# 36mm____V1_3.net
KiCad netlist of a schematic drawn in EasyEDA Pro
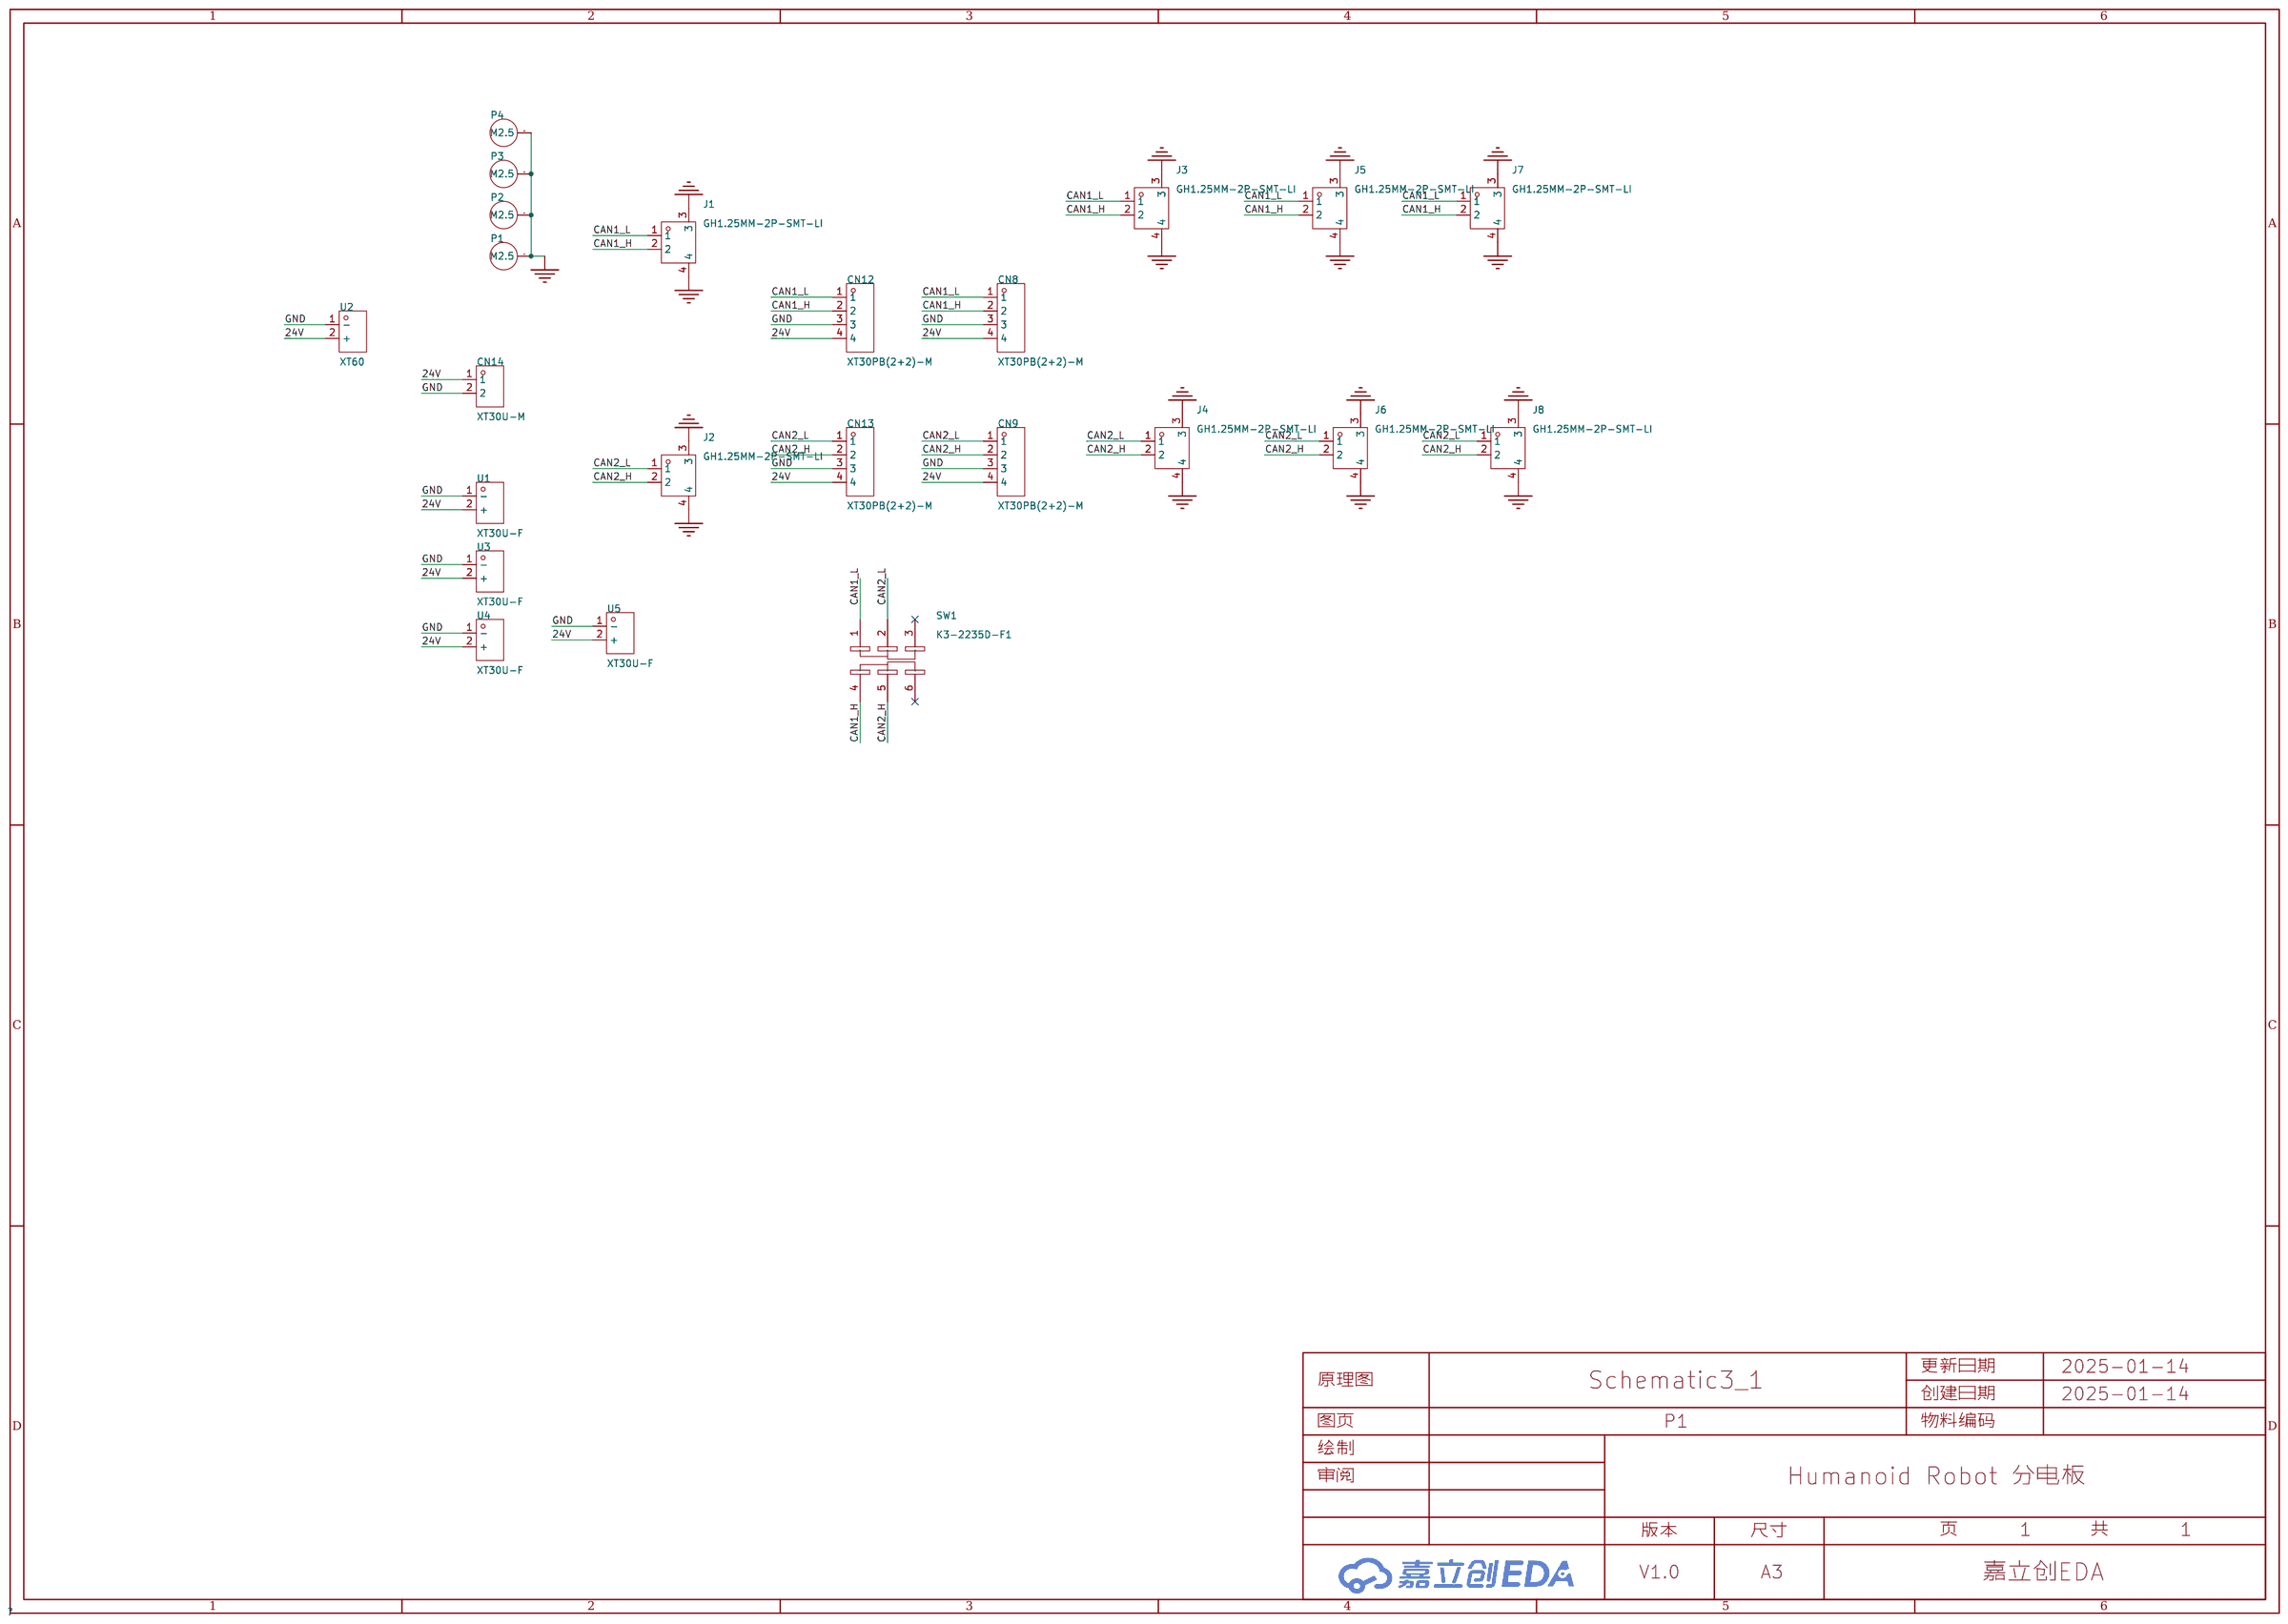
[diagram p0: schematic sheet]

(export (version "E")
  (design (tool "Eeschema 10.0.6"))
  (components
    (comp (ref "CN8")
      (value "XT30PB(2+2)-M")
      (footprint "easyedapro:CONN-TH_XT30PB-M")
      (fields (field (name "Manufacturer") "AMASS(艾迈斯)"))
      (libsource (lib "easyedapro") (part "XT30PB(2+2)-M"))
    )
    (comp (ref "CN9")
      (value "XT30PB(2+2)-M")
      (footprint "easyedapro:CONN-TH_XT30PB-M")
      (fields (field (name "Manufacturer") "AMASS(艾迈斯)"))
      (libsource (lib "easyedapro") (part "XT30PB(2+2)-M"))
    )
    (comp (ref "CN12")
      (value "XT30PB(2+2)-M")
      (footprint "easyedapro:CONN-TH_XT30PB-M")
      (fields (field (name "Manufacturer") "AMASS(艾迈斯)"))
      (libsource (lib "easyedapro") (part "XT30PB(2+2)-M"))
    )
    (comp (ref "CN13")
      (value "XT30PB(2+2)-M")
      (footprint "easyedapro:CONN-TH_XT30PB-M")
      (fields (field (name "Manufacturer") "AMASS(艾迈斯)"))
      (libsource (lib "easyedapro") (part "XT30PB(2+2)-M"))
    )
    (comp (ref "CN14")
      (value "XT30U-M")
      (footprint "easyedapro:CONN-TH_XT30U-M")
      (description "类别:-;类型1:-;")
      (fields (field (name "Manufacturer") "AMASS(艾迈斯)"))
      (libsource (lib "easyedapro") (part "XT30U-M"))
    )
    (comp (ref "J1")
      (value "GH1.25MM-2P-SMT-LI")
      (footprint "easyedapro:CONN-SMD_2P-P1.25_GH1.25-2PLI")
      (libsource (lib "easyedapro") (part "GH1.25MM-2P-SMT-LI"))
    )
    (comp (ref "J2")
      (value "GH1.25MM-2P-SMT-LI")
      (footprint "easyedapro:CONN-SMD_2P-P1.25_GH1.25-2PLI")
      (libsource (lib "easyedapro") (part "GH1.25MM-2P-SMT-LI"))
    )
    (comp (ref "J3")
      (value "GH1.25MM-2P-SMT-LI")
      (footprint "easyedapro:CONN-SMD_2P-P1.25_GH1.25-2PLI")
      (libsource (lib "easyedapro") (part "GH1.25MM-2P-SMT-LI"))
    )
    (comp (ref "J4")
      (value "GH1.25MM-2P-SMT-LI")
      (footprint "easyedapro:CONN-SMD_2P-P1.25_GH1.25-2PLI")
      (libsource (lib "easyedapro") (part "GH1.25MM-2P-SMT-LI"))
    )
    (comp (ref "J5")
      (value "GH1.25MM-2P-SMT-LI")
      (footprint "easyedapro:CONN-SMD_2P-P1.25_GH1.25-2PLI")
      (libsource (lib "easyedapro") (part "GH1.25MM-2P-SMT-LI"))
    )
    (comp (ref "J6")
      (value "GH1.25MM-2P-SMT-LI")
      (footprint "easyedapro:CONN-SMD_2P-P1.25_GH1.25-2PLI")
      (libsource (lib "easyedapro") (part "GH1.25MM-2P-SMT-LI"))
    )
    (comp (ref "J7")
      (value "GH1.25MM-2P-SMT-LI")
      (footprint "easyedapro:CONN-SMD_2P-P1.25_GH1.25-2PLI")
      (libsource (lib "easyedapro") (part "GH1.25MM-2P-SMT-LI"))
    )
    (comp (ref "J8")
      (value "GH1.25MM-2P-SMT-LI")
      (footprint "easyedapro:CONN-SMD_2P-P1.25_GH1.25-2PLI")
      (libsource (lib "easyedapro") (part "GH1.25MM-2P-SMT-LI"))
    )
    (comp (ref "P1")
      (value "~")
      (footprint "easyedapro:M2.5_PAD")
      (libsource (lib "easyedapro") (part "M2.5焊盘固定孔"))
    )
    (comp (ref "P2")
      (value "~")
      (footprint "easyedapro:M2.5_PAD")
      (libsource (lib "easyedapro") (part "M2.5焊盘固定孔"))
    )
    (comp (ref "P3")
      (value "~")
      (footprint "easyedapro:M2.5_PAD")
      (libsource (lib "easyedapro") (part "M2.5焊盘固定孔"))
    )
    (comp (ref "P4")
      (value "~")
      (footprint "easyedapro:M2.5_PAD")
      (libsource (lib "easyedapro") (part "M2.5焊盘固定孔"))
    )
    (comp (ref "SW1")
      (value "K3-2235D-F1")
      (footprint "easyedapro:SW-TH_K3-2235D-F1")
      (description "电路结构:双刀双掷;安装方式:直插;开关颜色:黑色;额定电流(DC):300mA;额定电压(DC):6V;额定电流(AC):-;额定电压(AC):-;机械寿命:1万次;")
      (fields (field (name "Manufacturer") "韩国韩荣"))
      (libsource (lib "easyedapro") (part "K3-2235D-F1"))
    )
    (comp (ref "U1")
      (value "XT30U-F")
      (footprint "easyedapro:CONN-TH_XT30U-F")
      (description "类别:-;类型1:-;")
      (fields (field (name "Manufacturer") "AMASS(艾迈斯)"))
      (libsource (lib "easyedapro") (part "XT30U-F"))
    )
    (comp (ref "U2")
      (value "XT60")
      (footprint "easyedapro:CONN-TH_XT60")
      (description "类别:-;类型1:-;")
      (fields (field (name "Manufacturer") "AMASS(艾迈斯)"))
      (libsource (lib "easyedapro") (part "XT60"))
    )
    (comp (ref "U3")
      (value "XT30U-F")
      (footprint "easyedapro:CONN-TH_XT30U-F")
      (description "类别:-;类型1:-;")
      (fields (field (name "Manufacturer") "AMASS(艾迈斯)"))
      (libsource (lib "easyedapro") (part "XT30U-F"))
    )
    (comp (ref "U4")
      (value "XT30U-F")
      (footprint "easyedapro:CONN-TH_XT30U-F")
      (description "类别:-;类型1:-;")
      (fields (field (name "Manufacturer") "AMASS(艾迈斯)"))
      (libsource (lib "easyedapro") (part "XT30U-F"))
    )
    (comp (ref "U5")
      (value "XT30U-F")
      (footprint "easyedapro:CONN-TH_XT30U-F")
      (description "类别:-;类型1:-;")
      (fields (field (name "Manufacturer") "AMASS(艾迈斯)"))
      (libsource (lib "easyedapro") (part "XT30U-F"))
    )
  )
  (nets
    (net (code "1") (name "/24V") (class "Default")
      (node (ref "CN12") (pin "4") (pinfunction "4_4") (pintype "unspecified"))
      (node (ref "CN13") (pin "4") (pinfunction "4_4") (pintype "unspecified"))
      (node (ref "CN14") (pin "1") (pinfunction "1_1") (pintype "unspecified"))
      (node (ref "CN8") (pin "4") (pinfunction "4_4") (pintype "unspecified"))
      (node (ref "CN9") (pin "4") (pinfunction "4_4") (pintype "unspecified"))
      (node (ref "U1") (pin "2") (pinfunction "+_2") (pintype "unspecified"))
      (node (ref "U2") (pin "2") (pinfunction "+_2") (pintype "unspecified"))
      (node (ref "U3") (pin "2") (pinfunction "+_2") (pintype "unspecified"))
      (node (ref "U4") (pin "2") (pinfunction "+_2") (pintype "unspecified"))
      (node (ref "U5") (pin "2") (pinfunction "+_2") (pintype "unspecified"))
    )
    (net (code "2") (name "/CAN1_H") (class "Default")
      (node (ref "CN12") (pin "2") (pinfunction "2_2") (pintype "unspecified"))
      (node (ref "CN8") (pin "2") (pinfunction "2_2") (pintype "unspecified"))
      (node (ref "J1") (pin "2") (pinfunction "2_2") (pintype "unspecified"))
      (node (ref "J3") (pin "2") (pinfunction "2_2") (pintype "unspecified"))
      (node (ref "J5") (pin "2") (pinfunction "2_2") (pintype "unspecified"))
      (node (ref "J7") (pin "2") (pinfunction "2_2") (pintype "unspecified"))
      (node (ref "SW1") (pin "4") (pinfunction "4_4") (pintype "unspecified"))
    )
    (net (code "3") (name "/CAN1_L") (class "Default")
      (node (ref "CN12") (pin "1") (pinfunction "1_1") (pintype "unspecified"))
      (node (ref "CN8") (pin "1") (pinfunction "1_1") (pintype "unspecified"))
      (node (ref "J1") (pin "1") (pinfunction "1_1") (pintype "unspecified"))
      (node (ref "J3") (pin "1") (pinfunction "1_1") (pintype "unspecified"))
      (node (ref "J5") (pin "1") (pinfunction "1_1") (pintype "unspecified"))
      (node (ref "J7") (pin "1") (pinfunction "1_1") (pintype "unspecified"))
      (node (ref "SW1") (pin "1") (pinfunction "1_1") (pintype "unspecified"))
    )
    (net (code "4") (name "/CAN2_H") (class "Default")
      (node (ref "CN13") (pin "2") (pinfunction "2_2") (pintype "unspecified"))
      (node (ref "CN9") (pin "2") (pinfunction "2_2") (pintype "unspecified"))
      (node (ref "J2") (pin "2") (pinfunction "2_2") (pintype "unspecified"))
      (node (ref "J4") (pin "2") (pinfunction "2_2") (pintype "unspecified"))
      (node (ref "J6") (pin "2") (pinfunction "2_2") (pintype "unspecified"))
      (node (ref "J8") (pin "2") (pinfunction "2_2") (pintype "unspecified"))
      (node (ref "SW1") (pin "5") (pinfunction "5_5") (pintype "unspecified"))
    )
    (net (code "5") (name "/CAN2_L") (class "Default")
      (node (ref "CN13") (pin "1") (pinfunction "1_1") (pintype "unspecified"))
      (node (ref "CN9") (pin "1") (pinfunction "1_1") (pintype "unspecified"))
      (node (ref "J2") (pin "1") (pinfunction "1_1") (pintype "unspecified"))
      (node (ref "J4") (pin "1") (pinfunction "1_1") (pintype "unspecified"))
      (node (ref "J6") (pin "1") (pinfunction "1_1") (pintype "unspecified"))
      (node (ref "J8") (pin "1") (pinfunction "1_1") (pintype "unspecified"))
      (node (ref "SW1") (pin "2") (pinfunction "2_2") (pintype "unspecified"))
    )
    (net (code "6") (name "GND") (class "Default")
      (node (ref "CN12") (pin "3") (pinfunction "3_3") (pintype "unspecified"))
      (node (ref "CN13") (pin "3") (pinfunction "3_3") (pintype "unspecified"))
      (node (ref "CN14") (pin "2") (pinfunction "2_2") (pintype "unspecified"))
      (node (ref "CN8") (pin "3") (pinfunction "3_3") (pintype "unspecified"))
      (node (ref "CN9") (pin "3") (pinfunction "3_3") (pintype "unspecified"))
      (node (ref "J1") (pin "3") (pinfunction "3_3") (pintype "unspecified"))
      (node (ref "J1") (pin "4") (pinfunction "4_4") (pintype "unspecified"))
      (node (ref "J2") (pin "3") (pinfunction "3_3") (pintype "unspecified"))
      (node (ref "J2") (pin "4") (pinfunction "4_4") (pintype "unspecified"))
      (node (ref "J3") (pin "3") (pinfunction "3_3") (pintype "unspecified"))
      (node (ref "J3") (pin "4") (pinfunction "4_4") (pintype "unspecified"))
      (node (ref "J4") (pin "3") (pinfunction "3_3") (pintype "unspecified"))
      (node (ref "J4") (pin "4") (pinfunction "4_4") (pintype "unspecified"))
      (node (ref "J5") (pin "3") (pinfunction "3_3") (pintype "unspecified"))
      (node (ref "J5") (pin "4") (pinfunction "4_4") (pintype "unspecified"))
      (node (ref "J6") (pin "3") (pinfunction "3_3") (pintype "unspecified"))
      (node (ref "J6") (pin "4") (pinfunction "4_4") (pintype "unspecified"))
      (node (ref "J7") (pin "3") (pinfunction "3_3") (pintype "unspecified"))
      (node (ref "J7") (pin "4") (pinfunction "4_4") (pintype "unspecified"))
      (node (ref "J8") (pin "3") (pinfunction "3_3") (pintype "unspecified"))
      (node (ref "J8") (pin "4") (pinfunction "4_4") (pintype "unspecified"))
      (node (ref "P1") (pin "1") (pinfunction "M2.5_1") (pintype "unspecified"))
      (node (ref "P2") (pin "1") (pinfunction "M2.5_1") (pintype "unspecified"))
      (node (ref "P3") (pin "1") (pinfunction "M2.5_1") (pintype "unspecified"))
      (node (ref "P4") (pin "1") (pinfunction "M2.5_1") (pintype "unspecified"))
      (node (ref "U1") (pin "1") (pinfunction "-_1") (pintype "unspecified"))
      (node (ref "U2") (pin "1") (pinfunction "-_1") (pintype "unspecified"))
      (node (ref "U3") (pin "1") (pinfunction "-_1") (pintype "unspecified"))
      (node (ref "U4") (pin "1") (pinfunction "-_1") (pintype "unspecified"))
      (node (ref "U5") (pin "1") (pinfunction "-_1") (pintype "unspecified"))
    )
    (net (code "7") (name "unconnected-(SW1-Pad3)") (class "Default")
      (node (ref "SW1") (pin "3") (pinfunction "3_3") (pintype "unspecified+no_connect"))
    )
    (net (code "8") (name "unconnected-(SW1-Pad6)") (class "Default")
      (node (ref "SW1") (pin "6") (pinfunction "6_6") (pintype "unspecified+no_connect"))
    )
  )
)
